# UI.net
KiCad netlist of a schematic drawn in Altium Designer
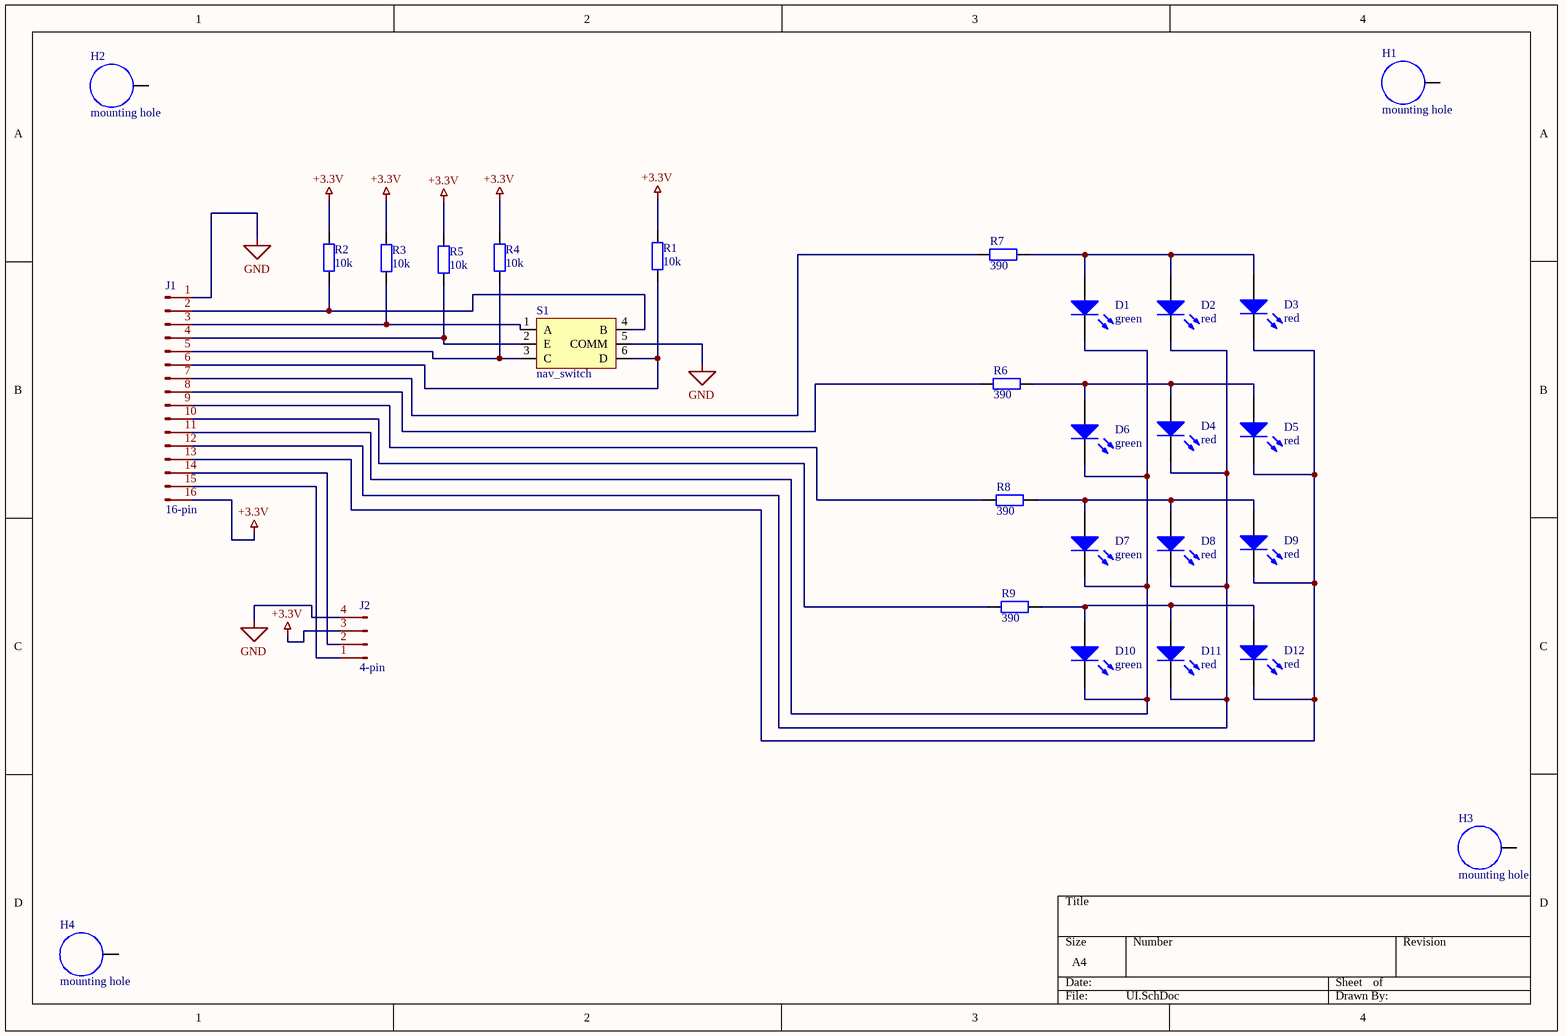
[diagram p0: UI.SchDoc]

(export (version "E")
  (design (tool "Eeschema 10.0.6"))
  (components
    (comp (ref "D1")
      (value "green")
      (footprint "0805 LED")
      (libsource (lib "generic_components") (part "LED"))
    )
    (comp (ref "D2") (value "red") (footprint "0805 LED") (libsource (lib "generic_components") (part "LED")))
    (comp (ref "D3") (value "red") (footprint "0805 LED") (libsource (lib "generic_components") (part "LED")))
    (comp (ref "D4") (value "red") (footprint "0805 LED") (libsource (lib "generic_components") (part "LED")))
    (comp (ref "D5") (value "red") (footprint "0805 LED") (libsource (lib "generic_components") (part "LED")))
    (comp (ref "D6")
      (value "green")
      (footprint "0805 LED")
      (libsource (lib "generic_components") (part "LED"))
    )
    (comp (ref "D7")
      (value "green")
      (footprint "0805 LED")
      (libsource (lib "generic_components") (part "LED"))
    )
    (comp (ref "D8") (value "red") (footprint "0805 LED") (libsource (lib "generic_components") (part "LED")))
    (comp (ref "D9") (value "red") (footprint "0805 LED") (libsource (lib "generic_components") (part "LED")))
    (comp (ref "D10")
      (value "green")
      (footprint "0805 LED")
      (libsource (lib "generic_components") (part "LED"))
    )
    (comp (ref "D11")
      (value "red")
      (footprint "0805 LED")
      (libsource (lib "generic_components") (part "LED"))
    )
    (comp (ref "D12")
      (value "red")
      (footprint "0805 LED")
      (libsource (lib "generic_components") (part "LED"))
    )
    (comp (ref "H1")
      (value "mounting hole")
      (footprint "M3 HOLE iso")
      (libsource (lib "generic_components") (part "mounting hole"))
    )
    (comp (ref "H2")
      (value "mounting hole")
      (footprint "M3 HOLE iso")
      (libsource (lib "generic_components") (part "mounting hole"))
    )
    (comp (ref "H3")
      (value "mounting hole")
      (footprint "M3 HOLE iso")
      (libsource (lib "generic_components") (part "mounting hole"))
    )
    (comp (ref "H4")
      (value "mounting hole")
      (footprint "M3 HOLE iso")
      (libsource (lib "generic_components") (part "mounting hole"))
    )
    (comp (ref "J1")
      (value "16-pin")
      (footprint "JST_XH_B16B-XH-A_1x16_P2.50mm_Vertical")
      (libsource (lib "JST") (part "16-pin"))
    )
    (comp (ref "J2")
      (value "4-pin")
      (footprint "JST_SH_SM04B-SRSS-TB_1x04-1MP_P1.00mm_Horizontal")
      (libsource (lib "JST") (part "4-pin"))
    )
    (comp (ref "R1") (value "10k") (footprint "0805") (libsource (lib "generic_components") (part "res0805")))
    (comp (ref "R2") (value "10k") (footprint "0805") (libsource (lib "generic_components") (part "res0805")))
    (comp (ref "R3") (value "10k") (footprint "0805") (libsource (lib "generic_components") (part "res0805")))
    (comp (ref "R4") (value "10k") (footprint "0805") (libsource (lib "generic_components") (part "res0805")))
    (comp (ref "R5") (value "10k") (footprint "0805") (libsource (lib "generic_components") (part "res0805")))
    (comp (ref "R6") (value "390") (footprint "0805") (libsource (lib "") (part "res0805_1")))
    (comp (ref "R7") (value "390") (footprint "0805") (libsource (lib "") (part "res0805_1")))
    (comp (ref "R8") (value "390") (footprint "0805") (libsource (lib "") (part "res0805_1")))
    (comp (ref "R9") (value "390") (footprint "0805") (libsource (lib "") (part "res0805_1")))
    (comp (ref "S1")
      (value "nav_switch")
      (footprint "NAV_SWITCH_SJ1400BFQ")
      (libsource (lib "generic_components") (part "nav_switch"))
    )
  )
  (nets
    (net (code "1") (name "+3.3V") (class "Default")
      (node (ref "J1") (pin "16") (pinfunction "Pin_16_16") (pintype "passive"))
      (node (ref "J2") (pin "3") (pinfunction "Pin_3_3") (pintype "passive"))
      (node (ref "R1") (pin "1") (pintype "passive"))
      (node (ref "R2") (pin "1") (pintype "passive"))
      (node (ref "R3") (pin "1") (pintype "passive"))
      (node (ref "R4") (pin "1") (pintype "passive"))
      (node (ref "R5") (pin "1") (pintype "passive"))
    )
    (net (code "2") (name "GND") (class "Default")
      (node (ref "J1") (pin "1") (pinfunction "Pin_1_1") (pintype "passive"))
      (node (ref "J2") (pin "4") (pinfunction "Pin_4_4") (pintype "passive"))
      (node (ref "S1") (pin "5") (pinfunction "COMM_5") (pintype "passive"))
    )
    (net (code "3") (name "Net-(D1-A)") (class "Default")
      (node (ref "D1") (pin "2") (pinfunction "A_2") (pintype "passive"))
      (node (ref "D2") (pin "2") (pinfunction "A_2") (pintype "passive"))
      (node (ref "D3") (pin "2") (pinfunction "A_2") (pintype "passive"))
      (node (ref "R7") (pin "2") (pinfunction "2_2") (pintype "passive"))
    )
    (net (code "4") (name "Net-(D1-K)") (class "Default")
      (node (ref "D1") (pin "1") (pinfunction "K_1") (pintype "passive"))
      (node (ref "D10") (pin "1") (pinfunction "K_1") (pintype "passive"))
      (node (ref "D6") (pin "1") (pinfunction "K_1") (pintype "passive"))
      (node (ref "D7") (pin "1") (pinfunction "K_1") (pintype "passive"))
      (node (ref "J1") (pin "11") (pinfunction "Pin_11_11") (pintype "passive"))
    )
    (net (code "5") (name "Net-(D4-A)") (class "Default")
      (node (ref "D4") (pin "2") (pinfunction "A_2") (pintype "passive"))
      (node (ref "D5") (pin "2") (pinfunction "A_2") (pintype "passive"))
      (node (ref "D6") (pin "2") (pinfunction "A_2") (pintype "passive"))
      (node (ref "R6") (pin "2") (pinfunction "2_2") (pintype "passive"))
    )
    (net (code "6") (name "Net-(D7-A)") (class "Default")
      (node (ref "D7") (pin "2") (pinfunction "A_2") (pintype "passive"))
      (node (ref "D8") (pin "2") (pinfunction "A_2") (pintype "passive"))
      (node (ref "D9") (pin "2") (pinfunction "A_2") (pintype "passive"))
      (node (ref "R8") (pin "2") (pinfunction "2_2") (pintype "passive"))
    )
    (net (code "7") (name "Net-(D10-A)") (class "Default")
      (node (ref "D10") (pin "2") (pinfunction "A_2") (pintype "passive"))
      (node (ref "D11") (pin "2") (pinfunction "A_2") (pintype "passive"))
      (node (ref "D12") (pin "2") (pinfunction "A_2") (pintype "passive"))
      (node (ref "R9") (pin "2") (pinfunction "2_2") (pintype "passive"))
    )
    (net (code "8") (name "Net-(D11-K)") (class "Default")
      (node (ref "D11") (pin "1") (pinfunction "K_1") (pintype "passive"))
      (node (ref "D2") (pin "1") (pinfunction "K_1") (pintype "passive"))
      (node (ref "D4") (pin "1") (pinfunction "K_1") (pintype "passive"))
      (node (ref "D8") (pin "1") (pinfunction "K_1") (pintype "passive"))
      (node (ref "J1") (pin "12") (pinfunction "Pin_12_12") (pintype "passive"))
    )
    (net (code "9") (name "Net-(D12-K)") (class "Default")
      (node (ref "D12") (pin "1") (pinfunction "K_1") (pintype "passive"))
      (node (ref "D3") (pin "1") (pinfunction "K_1") (pintype "passive"))
      (node (ref "D5") (pin "1") (pinfunction "K_1") (pintype "passive"))
      (node (ref "D9") (pin "1") (pinfunction "K_1") (pintype "passive"))
      (node (ref "J1") (pin "13") (pinfunction "Pin_13_13") (pintype "passive"))
    )
    (net (code "10") (name "Net-(J1-Pin_2)") (class "Default")
      (node (ref "J1") (pin "2") (pinfunction "Pin_2_2") (pintype "passive"))
      (node (ref "R2") (pin "2") (pinfunction "2_2") (pintype "passive"))
      (node (ref "S1") (pin "4") (pinfunction "B_4") (pintype "passive"))
    )
    (net (code "11") (name "Net-(J1-Pin_3)") (class "Default")
      (node (ref "J1") (pin "3") (pinfunction "Pin_3_3") (pintype "passive"))
      (node (ref "R3") (pin "2") (pinfunction "2_2") (pintype "passive"))
      (node (ref "S1") (pin "1") (pinfunction "A_1") (pintype "passive"))
    )
    (net (code "12") (name "Net-(J1-Pin_4)") (class "Default")
      (node (ref "J1") (pin "4") (pinfunction "Pin_4_4") (pintype "passive"))
      (node (ref "R5") (pin "2") (pinfunction "2_2") (pintype "passive"))
      (node (ref "S1") (pin "2") (pinfunction "E_2") (pintype "passive"))
    )
    (net (code "13") (name "Net-(J1-Pin_5)") (class "Default")
      (node (ref "J1") (pin "5") (pinfunction "Pin_5_5") (pintype "passive"))
      (node (ref "R4") (pin "2") (pinfunction "2_2") (pintype "passive"))
      (node (ref "S1") (pin "3") (pinfunction "C_3") (pintype "passive"))
    )
    (net (code "14") (name "Net-(J1-Pin_6)") (class "Default")
      (node (ref "J1") (pin "6") (pinfunction "Pin_6_6") (pintype "passive"))
      (node (ref "R1") (pin "2") (pinfunction "2_2") (pintype "passive"))
      (node (ref "S1") (pin "6") (pinfunction "D_6") (pintype "passive"))
    )
    (net (code "15") (name "Net-(J1-Pin_7)") (class "Default")
      (node (ref "J1") (pin "7") (pinfunction "Pin_7_7") (pintype "passive"))
      (node (ref "R7") (pin "1") (pintype "passive"))
    )
    (net (code "16") (name "Net-(J1-Pin_8)") (class "Default")
      (node (ref "J1") (pin "8") (pinfunction "Pin_8_8") (pintype "passive"))
      (node (ref "R6") (pin "1") (pintype "passive"))
    )
    (net (code "17") (name "Net-(J1-Pin_9)") (class "Default")
      (node (ref "J1") (pin "9") (pinfunction "Pin_9_9") (pintype "passive"))
      (node (ref "R8") (pin "1") (pintype "passive"))
    )
    (net (code "18") (name "Net-(J1-Pin_10)") (class "Default")
      (node (ref "J1") (pin "10") (pinfunction "Pin_10_10") (pintype "passive"))
      (node (ref "R9") (pin "1") (pintype "passive"))
    )
    (net (code "19") (name "Net-(J1-Pin_14)") (class "Default")
      (node (ref "J1") (pin "14") (pinfunction "Pin_14_14") (pintype "passive"))
      (node (ref "J2") (pin "2") (pinfunction "Pin_2_2") (pintype "passive"))
    )
    (net (code "20") (name "Net-(J1-Pin_15)") (class "Default")
      (node (ref "J1") (pin "15") (pinfunction "Pin_15_15") (pintype "passive"))
      (node (ref "J2") (pin "1") (pinfunction "Pin_1_1") (pintype "passive"))
    )
    (net (code "21") (name "unconnected-(H1-Pad1)") (class "Default")
      (node (ref "H1") (pin "1") (pintype "passive"))
    )
    (net (code "22") (name "unconnected-(H2-Pad1)") (class "Default")
      (node (ref "H2") (pin "1") (pintype "passive"))
    )
    (net (code "23") (name "unconnected-(H3-Pad1)") (class "Default")
      (node (ref "H3") (pin "1") (pintype "passive"))
    )
    (net (code "24") (name "unconnected-(H4-Pad1)") (class "Default")
      (node (ref "H4") (pin "1") (pintype "passive"))
    )
  )
)
